# N17V5_Reference.net
KiCad netlist of a schematic drawn in Altium Designer
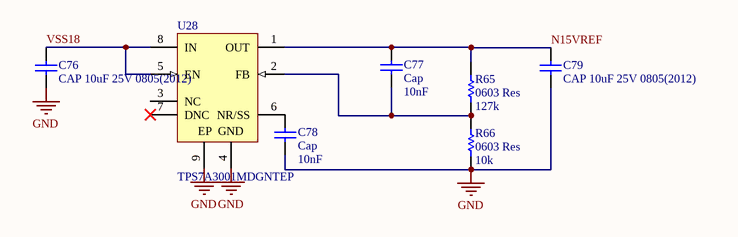
[diagram p0: N17V5 Reference.SchDoc]

(export (version "E")
  (design (tool "Eeschema 10.0.6"))
  (components
    (comp (ref "C76")
      (value "CAP 10uF 25V 0805(2012)")
      (footprint "CAPC0805(2012)145_N")
      (description "CAP 10uF 25V ±10% 0805 (2012 Metric) Thickness 1.45mm SMD")
      (fields (field (name "TOLERANCE") "Â±10%"))
      (libsource (lib "Altium Content Vault") (part "CAP"))
    )
    (comp (ref "C77")
      (value "Cap")
      (footprint "1608[0603]")
      (description "Capacitor")
      (fields (field (name "ALTIUM_VALUE") "10nF") (field (name "PUBLISHER") "Altium Limited"))
      (libsource (lib "Miscellaneous Devices") (part "Cap"))
    )
    (comp (ref "C78")
      (value "Cap")
      (footprint "1608[0603]")
      (description "Capacitor")
      (fields (field (name "ALTIUM_VALUE") "10nF") (field (name "PUBLISHER") "Altium Limited"))
      (libsource (lib "Miscellaneous Devices") (part "Cap"))
    )
    (comp (ref "C79")
      (value "CAP 10uF 25V 0805(2012)")
      (footprint "CAPC0805(2012)145_N")
      (description "CAP 10uF 25V ±10% 0805 (2012 Metric) Thickness 1.45mm SMD")
      (fields (field (name "TOLERANCE") "Â±10%"))
      (libsource (lib "Altium Content Vault") (part "CAP"))
    )
    (comp (ref "R65")
      (value "0603 Res")
      (footprint "J1-0603")
      (description "Chip Resistor, 0603, 1%")
      (fields (field (name "ALTIUM_VALUE") "127k") (field (name "PUBLISHER") "Altium Limited"))
      (libsource (lib "Miscellaneous Devices") (part "Res1"))
    )
    (comp (ref "R66")
      (value "0603 Res")
      (footprint "J1-0603")
      (description "Chip Resistor, 0603, 1%")
      (fields (field (name "ALTIUM_VALUE") "10k") (field (name "PUBLISHER") "Altium Limited"))
      (libsource (lib "Miscellaneous Devices") (part "Res1"))
    )
    (comp (ref "U28")
      (value "TPS7A3001MDGNTEP")
      (footprint "DGN0008D_M")
      (fields (field (name "MANUFACTURER") "Texas Instruments"))
      (libsource (lib "Altium Content Vault") (part "TI-TPS7AXX01-YYDGN8-1760X1425TP"))
    )
  )
  (nets
    (net (code "1") (name "/N15VREF") (class "Default")
      (node (ref "C77") (pin "2") (pinfunction "2_2") (pintype "passive"))
      (node (ref "C79") (pin "2") (pinfunction "2_2") (pintype "passive"))
      (node (ref "R65") (pin "1") (pinfunction "1_1") (pintype "passive"))
      (node (ref "U28") (pin "1") (pinfunction "OUT_1") (pintype "power_in"))
    )
    (net (code "2") (name "/VSS18") (class "Default")
      (node (ref "C76") (pin "2") (pinfunction "2_2") (pintype "passive"))
      (node (ref "U28") (pin "5") (pinfunction "EN_5") (pintype "input"))
      (node (ref "U28") (pin "8") (pinfunction "IN_8") (pintype "power_in"))
    )
    (net (code "3") (name "GND") (class "Default")
      (node (ref "C76") (pin "1") (pinfunction "1_1") (pintype "passive"))
      (node (ref "C78") (pin "1") (pinfunction "1_1") (pintype "passive"))
      (node (ref "C79") (pin "1") (pinfunction "1_1") (pintype "passive"))
      (node (ref "R66") (pin "2") (pinfunction "2_2") (pintype "passive"))
      (node (ref "U28") (pin "4") (pinfunction "GND_4") (pintype "power_in"))
      (node (ref "U28") (pin "9") (pinfunction "EP_9") (pintype "power_in"))
    )
    (net (code "4") (name "Net-(U28-FB)") (class "Default")
      (node (ref "C77") (pin "1") (pinfunction "1_1") (pintype "passive"))
      (node (ref "R65") (pin "2") (pinfunction "2_2") (pintype "passive"))
      (node (ref "R66") (pin "1") (pinfunction "1_1") (pintype "passive"))
      (node (ref "U28") (pin "2") (pinfunction "FB_2") (pintype "input"))
    )
    (net (code "5") (name "Net-(U28-NR{slash}SS)") (class "Default")
      (node (ref "C78") (pin "2") (pinfunction "2_2") (pintype "passive"))
      (node (ref "U28") (pin "6") (pinfunction "NR/SS_6") (pintype "passive"))
    )
    (net (code "6") (name "unconnected-(U28-DNC-Pad7)") (class "Default")
      (node (ref "U28") (pin "7") (pinfunction "DNC_7") (pintype "passive+no_connect"))
    )
    (net (code "7") (name "unconnected-(U28-NC-Pad3)") (class "Default")
      (node (ref "U28") (pin "3") (pinfunction "NC_3") (pintype "passive"))
    )
  )
)
